# Buddy.net
KiCad netlist of a schematic drawn in Altium Designer
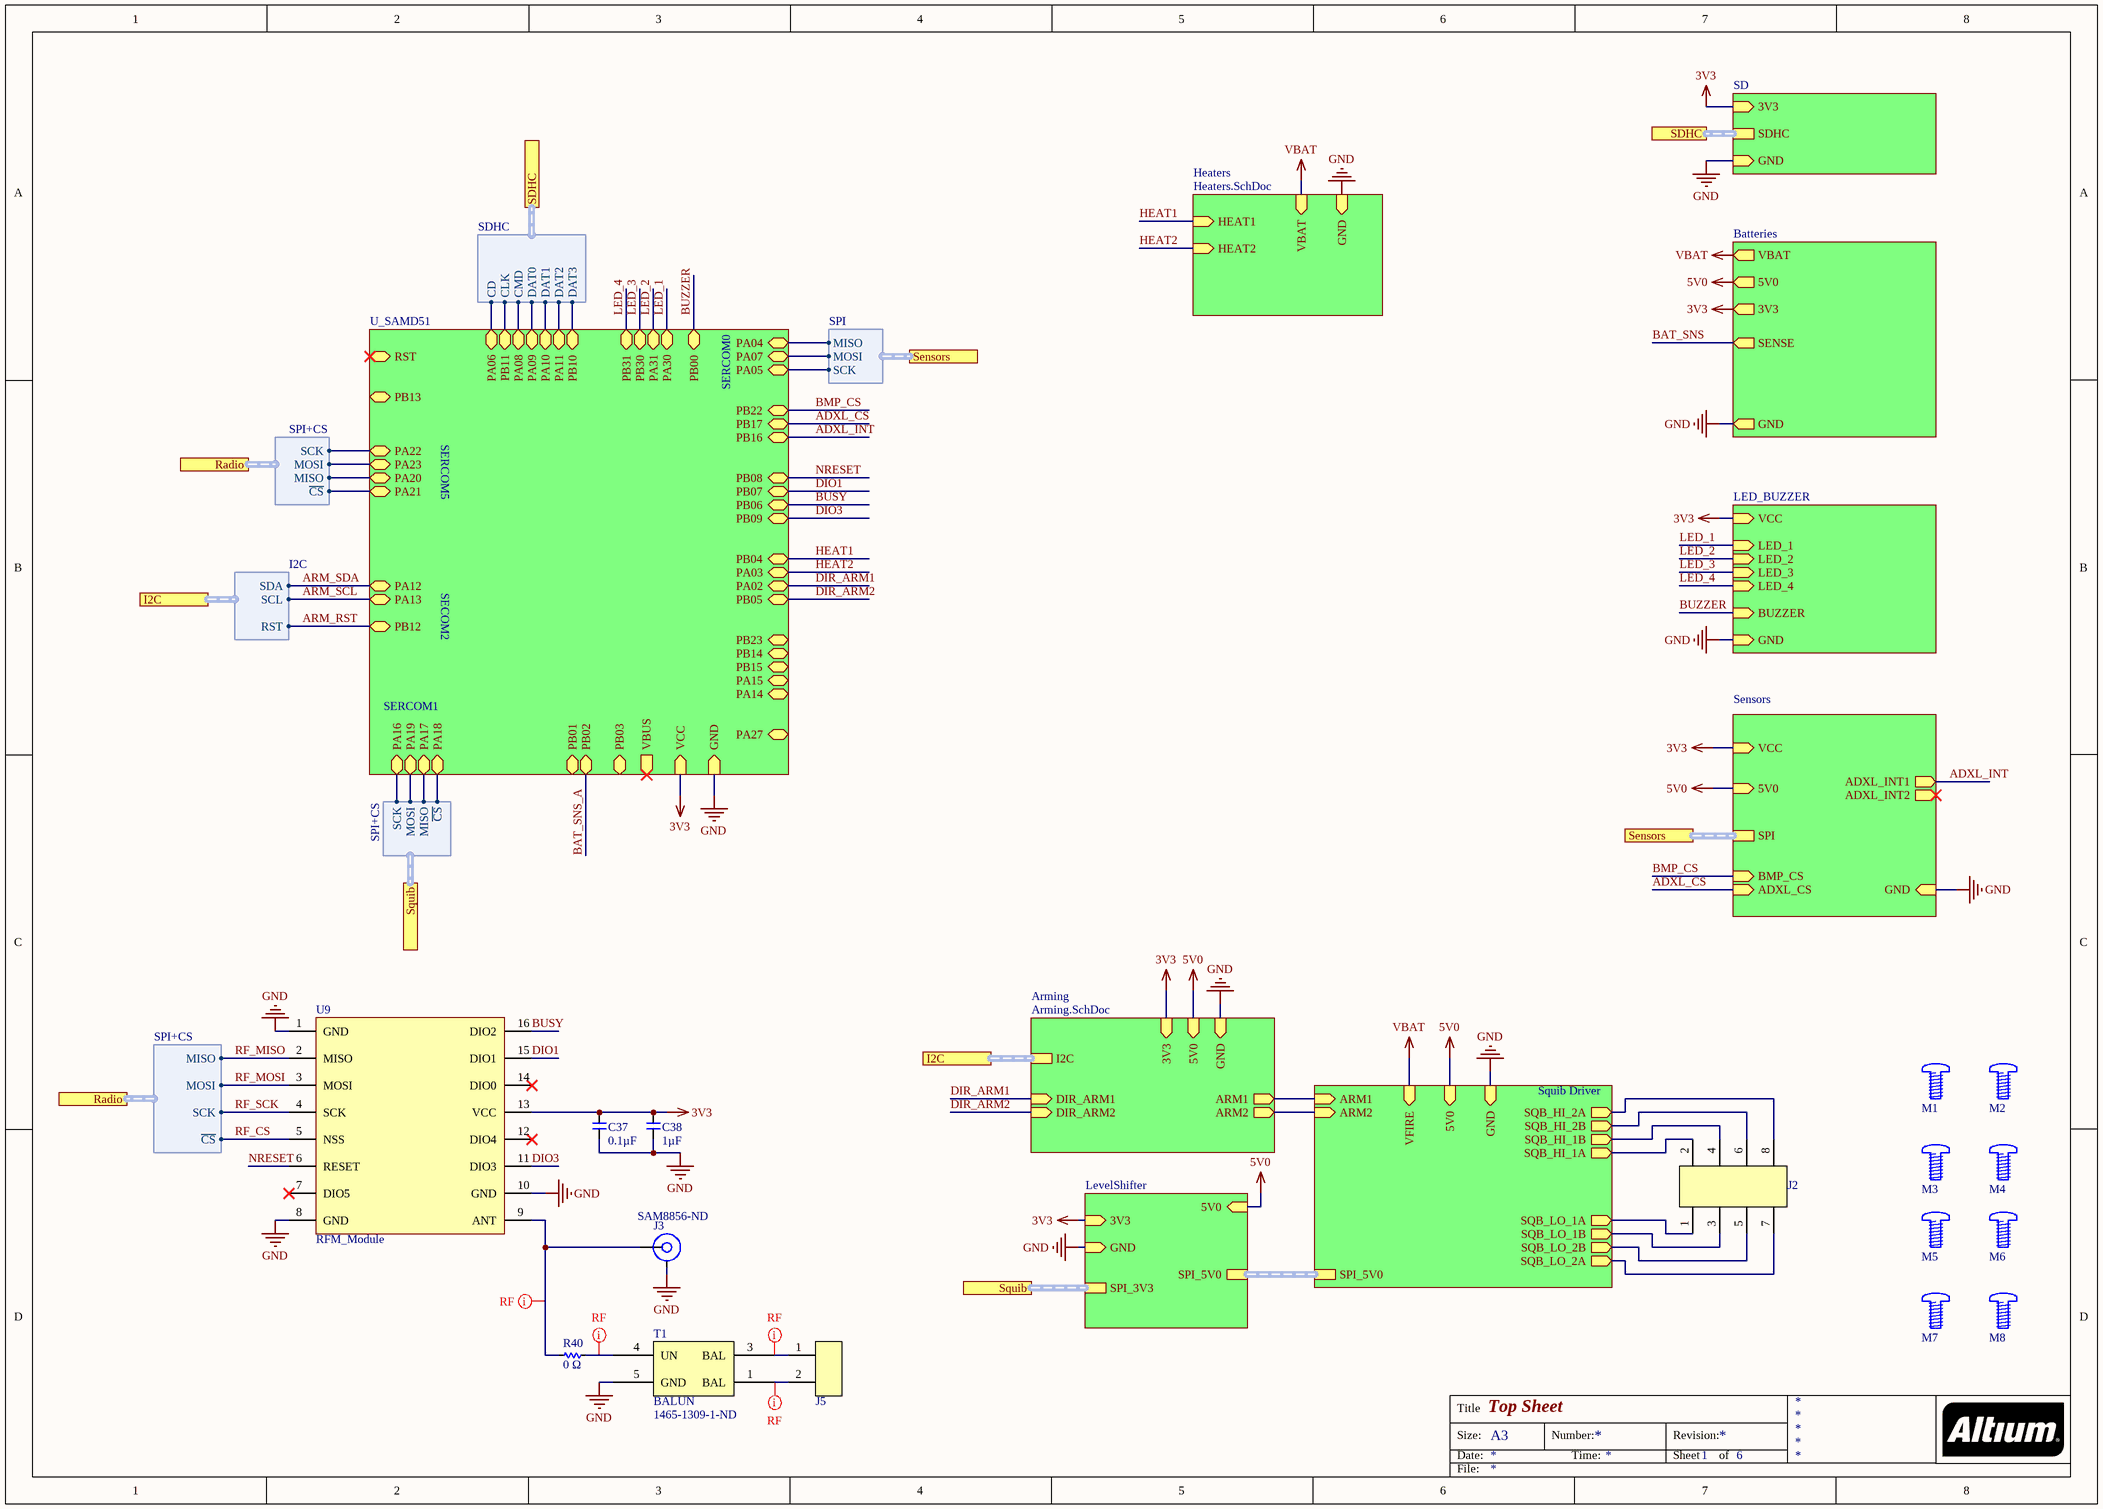
[diagram p0: Buddy.SchDoc]

(export (version "E")
  (design (tool "Eeschema 10.0.6"))
  (components
    (comp (ref "C37")
      (value "__template_cap")
      (footprint "C0603")
      (description "CAP CER 0603 0.1µF X7R 50V 10%")
      (fields
        (field (name "CAPACITANCE (SHORTHAND)") "0.1µF")
        (field (name "MANUFACTURER") "Murata Electronics North America")
      )
      (libsource (lib "passives") (part "__template_cap"))
    )
    (comp (ref "C38")
      (value "__template_cap")
      (footprint "C0603")
      (description "CAP CER 0603 1µF X7R 16V 10%")
      (fields
        (field (name "CAPACITANCE (SHORTHAND)") "1µF")
        (field (name "MANUFACTURER") "Murata Electronics North America")
      )
      (libsource (lib "passives") (part "__template_cap"))
    )
    (comp (ref "J2")
      (value "CONN_2x4_Harwin-M80-5T108")
      (footprint "Harwin M80-5T108")
      (libsource (lib "SSI") (part "CONN_2x4_Harwin-M80-5T108"))
    )
    (comp (ref "J3")
      (value "SMA_SAMTEC_TH_RA")
      (footprint "SMA_SAMTEC_SMA-J-P-X-RA-TH1")
      (fields (field (name "SUPPLIER PART NUMBER 1") "SAM8856-ND"))
      (libsource (lib "SSI") (part "SMA_SAMTEC_TH_RA"))
    )
    (comp (ref "J5")
      (value "CONN HEADER 2POS VERT T/H")
      (footprint "CONN_1x2_100MIL")
      (fields (field (name "MANUFACTURER") "FCI") (field (name "MANUFACTURER PART NUMBER") "77311-118-02LF"))
      (libsource (lib "SSI") (part "CONN_1x2"))
    )
    (comp (ref "M1")
      (value "SCREW_#4-40")
      (footprint "#4_HOLE")
      (description "#4-40 Button Head Screw")
      (libsource (lib "SSI") (part "SCREW_#4-40"))
    )
    (comp (ref "M2")
      (value "SCREW_#4-40")
      (footprint "#4_HOLE")
      (description "#4-40 Button Head Screw")
      (libsource (lib "SSI") (part "SCREW_#4-40"))
    )
    (comp (ref "M3")
      (value "SCREW_#4-40")
      (footprint "#4_HOLE")
      (description "#4-40 Button Head Screw")
      (libsource (lib "SSI") (part "SCREW_#4-40"))
    )
    (comp (ref "M4")
      (value "SCREW_#4-40")
      (footprint "#4_HOLE")
      (description "#4-40 Button Head Screw")
      (libsource (lib "SSI") (part "SCREW_#4-40"))
    )
    (comp (ref "M5")
      (value "SCREW_#4-40")
      (footprint "#4_HOLE")
      (description "#4-40 Button Head Screw")
      (libsource (lib "SSI") (part "SCREW_#4-40"))
    )
    (comp (ref "M6")
      (value "SCREW_#4-40")
      (footprint "#4_HOLE")
      (description "#4-40 Button Head Screw")
      (libsource (lib "SSI") (part "SCREW_#4-40"))
    )
    (comp (ref "M7")
      (value "SCREW_#4-40")
      (footprint "#4_HOLE")
      (description "#4-40 Button Head Screw")
      (libsource (lib "SSI") (part "SCREW_#4-40"))
    )
    (comp (ref "M8")
      (value "SCREW_#4-40")
      (footprint "#4_HOLE")
      (description "#4-40 Button Head Screw")
      (libsource (lib "SSI") (part "SCREW_#4-40"))
    )
    (comp (ref "R40")
      (value "__template_resistor")
      (footprint "R0402")
      (description "RES SMD 0 OHM JUMPER 1/16W 0402")
      (fields
        (field (name "RESISTANCE") "0 Ω")
        (field (name "MANUFACTURER PART NUMBER") "RC0402FR-070RL")
        (field (name "MANUFACTURER") "Yageo")
      )
      (libsource (lib "passives") (part "__template_resistor"))
    )
    (comp (ref "T1")
      (value "BALUN")
      (footprint "BALUN_MABA-010245-CT1160")
      (fields (field (name "SUPPLIER PART NUMBER 1") "1465-1309-1-ND"))
      (libsource (lib "SSI") (part "BALUN"))
    )
    (comp (ref "U9") (value "RFM_Module") (footprint "RFM-22") (libsource (lib "SSI") (part "RFM_Module")))
  )
  (nets
    (net (code "15") (name "/BUSY") (class "Default")
      (node (ref "U9") (pin "16") (pinfunction "DIO2_16") (pintype "passive"))
    )
    (net (code "17") (name "/DIO1") (class "Default")
      (node (ref "U9") (pin "15") (pinfunction "DIO1_15") (pintype "passive"))
    )
    (net (code "18") (name "/DIO3") (class "Default")
      (node (ref "U9") (pin "11") (pinfunction "DIO3_11") (pintype "passive"))
    )
    (net (code "27") (name "/NRESET") (class "Default")
      (node (ref "U9") (pin "6") (pinfunction "RESET_6") (pintype "passive"))
    )
    (net (code "55") (name "/RF_CS") (class "Default")
      (node (ref "U9") (pin "5") (pinfunction "NSS_5") (pintype "passive"))
    )
    (net (code "56") (name "/RF_MISO") (class "Default")
      (node (ref "U9") (pin "2") (pinfunction "MISO_2") (pintype "passive"))
    )
    (net (code "57") (name "/RF_MOSI") (class "Default")
      (node (ref "U9") (pin "3") (pinfunction "MOSI_3") (pintype "passive"))
    )
    (net (code "58") (name "/RF_SCK") (class "Default")
      (node (ref "U9") (pin "4") (pinfunction "SCK_4") (pintype "passive"))
    )
    (net (code "62") (name "/SQB_HI_1A") (class "Default")
      (node (ref "J2") (pin "2") (pinfunction "2_2") (pintype "passive"))
    )
    (net (code "63") (name "/SQB_HI_1B") (class "Default")
      (node (ref "J2") (pin "4") (pinfunction "4_4") (pintype "passive"))
    )
    (net (code "64") (name "/SQB_HI_2A") (class "Default")
      (node (ref "J2") (pin "8") (pinfunction "8_8") (pintype "passive"))
    )
    (net (code "65") (name "/SQB_HI_2B") (class "Default")
      (node (ref "J2") (pin "6") (pinfunction "6_6") (pintype "passive"))
    )
    (net (code "66") (name "/SQB_LO_1A") (class "Default")
      (node (ref "J2") (pin "1") (pinfunction "1_1") (pintype "passive"))
    )
    (net (code "67") (name "/SQB_LO_1B") (class "Default")
      (node (ref "J2") (pin "3") (pinfunction "3_3") (pintype "passive"))
    )
    (net (code "68") (name "/SQB_LO_2A") (class "Default")
      (node (ref "J2") (pin "7") (pinfunction "7_7") (pintype "passive"))
    )
    (net (code "69") (name "/SQB_LO_2B") (class "Default")
      (node (ref "J2") (pin "5") (pinfunction "5_5") (pintype "passive"))
    )
    (net (code "75") (name "3V3") (class "Default")
      (node (ref "C37") (pin "1") (pintype "passive"))
      (node (ref "C38") (pin "1") (pintype "passive"))
      (node (ref "U9") (pin "13") (pinfunction "VCC_13") (pintype "passive"))
    )
    (net (code "77") (name "GND") (class "Default")
      (node (ref "C37") (pin "2") (pintype "passive"))
      (node (ref "C38") (pin "2") (pintype "passive"))
      (node (ref "J3") (pin "GND") (pinfunction "GND_GND") (pintype "passive"))
      (node (ref "T1") (pin "5") (pinfunction "GND_5") (pintype "passive"))
      (node (ref "U9") (pin "1") (pinfunction "GND_1") (pintype "passive"))
      (node (ref "U9") (pin "10") (pinfunction "GND_10") (pintype "passive"))
      (node (ref "U9") (pin "8") (pinfunction "GND_8") (pintype "passive"))
    )
    (net (code "78") (name "Net-(J5-Pad1)") (class "Default")
      (node (ref "J5") (pin "1") (pinfunction "1_1") (pintype "passive"))
      (node (ref "T1") (pin "3") (pinfunction "BAL_3") (pintype "passive"))
    )
    (net (code "79") (name "Net-(J5-Pad2)") (class "Default")
      (node (ref "J5") (pin "2") (pinfunction "2_2") (pintype "passive"))
      (node (ref "T1") (pin "1") (pinfunction "BAL_1") (pintype "passive"))
    )
    (net (code "80") (name "Net-(T1-UN)") (class "Default")
      (node (ref "R40") (pin "2") (pintype "passive"))
      (node (ref "T1") (pin "4") (pinfunction "UN_4") (pintype "passive"))
    )
    (net (code "81") (name "Net-(U9-ANT)") (class "Default")
      (node (ref "J3") (pin "SIG") (pinfunction "SIG_SIG") (pintype "passive"))
      (node (ref "R40") (pin "1") (pintype "passive"))
      (node (ref "U9") (pin "9") (pinfunction "ANT_9") (pintype "passive"))
    )
    (net (code "83") (name "unconnected-(M1-0-PadHOLE)") (class "Default")
      (node (ref "M1") (pin "HOLE") (pinfunction "0_HOLE") (pintype "passive"))
    )
    (net (code "84") (name "unconnected-(M2-0-PadHOLE)") (class "Default")
      (node (ref "M2") (pin "HOLE") (pinfunction "0_HOLE") (pintype "passive"))
    )
    (net (code "85") (name "unconnected-(M3-0-PadHOLE)") (class "Default")
      (node (ref "M3") (pin "HOLE") (pinfunction "0_HOLE") (pintype "passive"))
    )
    (net (code "86") (name "unconnected-(M4-0-PadHOLE)") (class "Default")
      (node (ref "M4") (pin "HOLE") (pinfunction "0_HOLE") (pintype "passive"))
    )
    (net (code "87") (name "unconnected-(M5-0-PadHOLE)") (class "Default")
      (node (ref "M5") (pin "HOLE") (pinfunction "0_HOLE") (pintype "passive"))
    )
    (net (code "88") (name "unconnected-(M6-0-PadHOLE)") (class "Default")
      (node (ref "M6") (pin "HOLE") (pinfunction "0_HOLE") (pintype "passive"))
    )
    (net (code "89") (name "unconnected-(M7-0-PadHOLE)") (class "Default")
      (node (ref "M7") (pin "HOLE") (pinfunction "0_HOLE") (pintype "passive"))
    )
    (net (code "90") (name "unconnected-(M8-0-PadHOLE)") (class "Default")
      (node (ref "M8") (pin "HOLE") (pinfunction "0_HOLE") (pintype "passive"))
    )
    (net (code "91") (name "unconnected-(U9-DIO0-Pad14)") (class "Default")
      (node (ref "U9") (pin "14") (pinfunction "DIO0_14") (pintype "passive+no_connect"))
    )
    (net (code "92") (name "unconnected-(U9-DIO4-Pad12)") (class "Default")
      (node (ref "U9") (pin "12") (pinfunction "DIO4_12") (pintype "passive+no_connect"))
    )
    (net (code "93") (name "unconnected-(U9-DIO5-Pad7)") (class "Default")
      (node (ref "U9") (pin "7") (pinfunction "DIO5_7") (pintype "passive+no_connect"))
    )
  )
)
